# FlashPanelV6_2.net
KiCad netlist of a schematic drawn in EAGLE
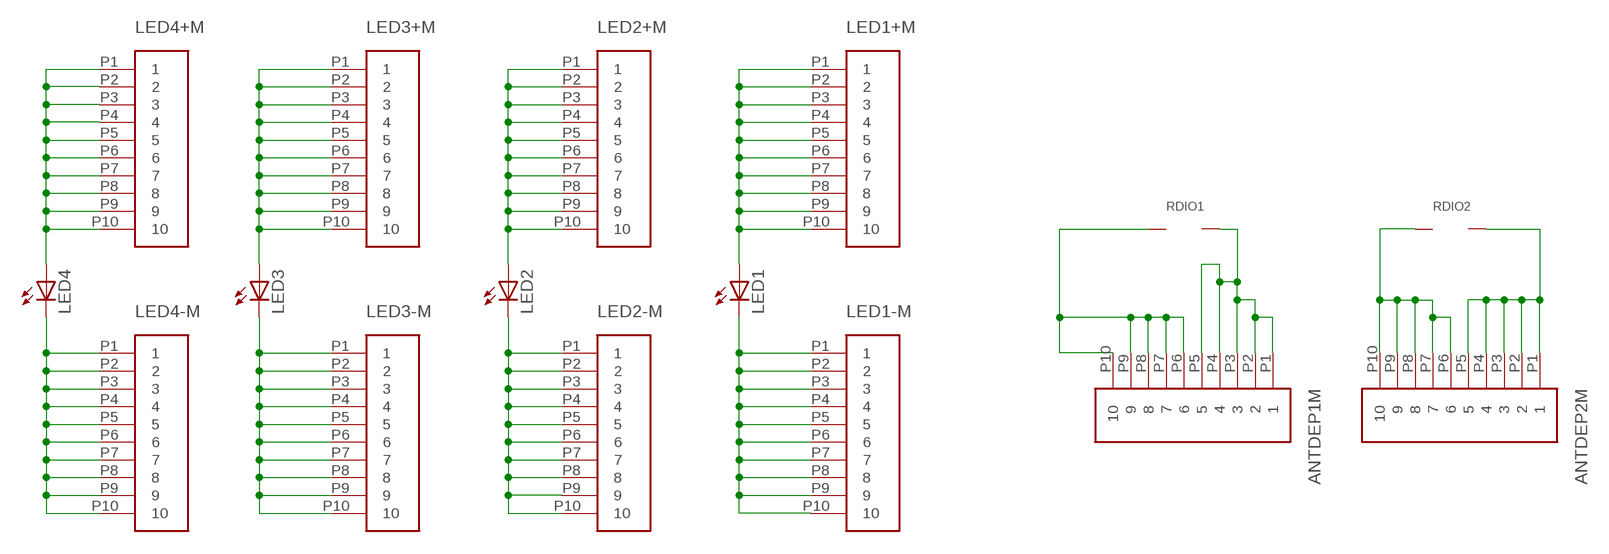
[diagram p0: schematic, sheet 1, part 1 of 2]
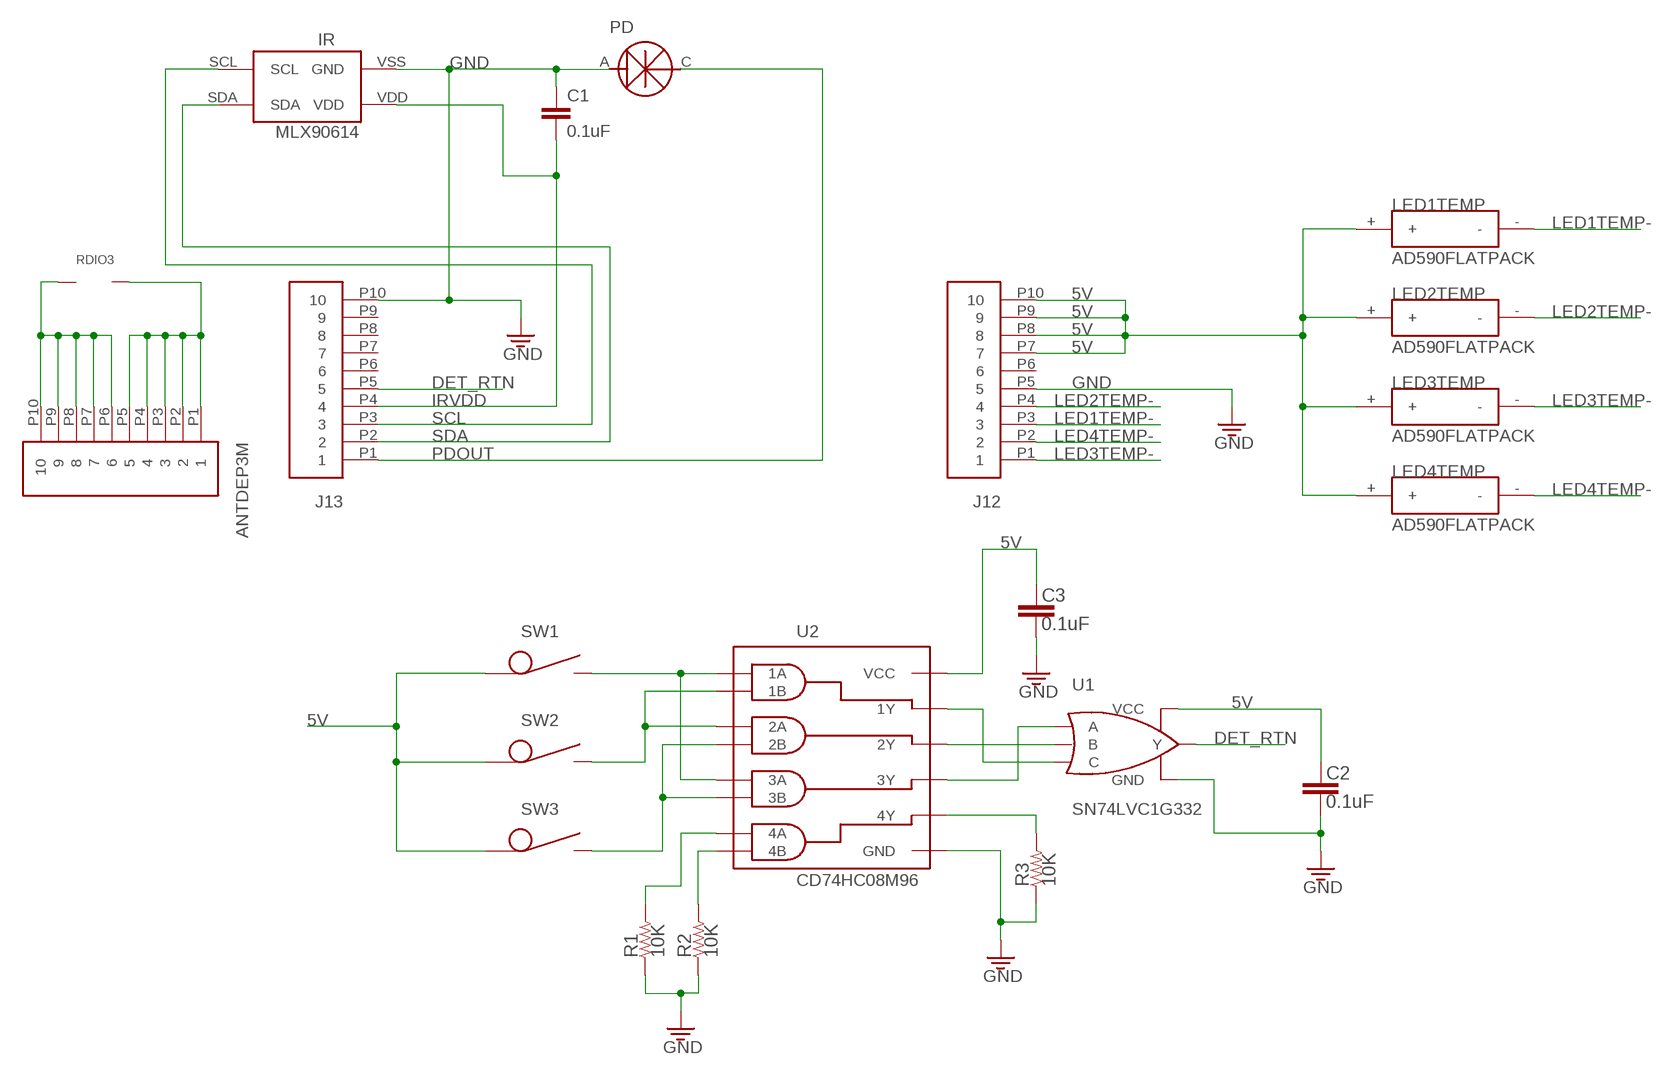
[diagram p1: schematic, sheet 1, part 2 of 2]

(export (version "E")
  (design (tool "Eeschema 10.0.6"))
  (components
    (comp (ref "ANTDEP1M")
      (value "10PINMALE")
      (footprint "eagle-import:10PINMALE")
      (libsource (lib "eagle-import") (part "10PINMALE"))
    )
    (comp (ref "ANTDEP2M")
      (value "10PINMALE")
      (footprint "eagle-import:10PINMALE")
      (libsource (lib "eagle-import") (part "10PINMALE"))
    )
    (comp (ref "ANTDEP3M")
      (value "10PINMALE")
      (footprint "eagle-import:10PINMALE")
      (libsource (lib "eagle-import") (part "10PINMALE"))
    )
    (comp (ref "C1")
      (value "0.1uF")
      (footprint "eagle-import:0805")
      (libsource (lib "eagle-import") (part "CNTRL_BOARD_CAP0805"))
    )
    (comp (ref "C2")
      (value "0.1uF")
      (footprint "eagle-import:0805")
      (libsource (lib "eagle-import") (part "CAP0805"))
    )
    (comp (ref "C3")
      (value "0.1uF")
      (footprint "eagle-import:0805")
      (libsource (lib "eagle-import") (part "CAP0805"))
    )
    (comp (ref "IR")
      (value "MXL90614")
      (footprint "eagle-import:MXL90620")
      (libsource (lib "eagle-import") (part "MXL90614"))
    )
    (comp (ref "J12")
      (value "10PINMALE")
      (footprint "eagle-import:10PINMALE")
      (libsource (lib "eagle-import") (part "10PINMALE"))
    )
    (comp (ref "J13")
      (value "10PINMALE")
      (footprint "eagle-import:10PINMALE")
      (libsource (lib "eagle-import") (part "10PINMALE"))
    )
    (comp (ref "LED1")
      (value "CXM27")
      (footprint "eagle-import:CXM27")
      (libsource (lib "eagle-import") (part "CXM27"))
    )
    (comp (ref "LED1+M")
      (value "10PINMALE")
      (footprint "eagle-import:10PINMALE")
      (libsource (lib "eagle-import") (part "10PINMALE"))
    )
    (comp (ref "LED1-M")
      (value "10PINMALE")
      (footprint "eagle-import:10PINMALE")
      (libsource (lib "eagle-import") (part "10PINMALE"))
    )
    (comp (ref "LED1TEMP")
      (value "AD590FLATPACK")
      (footprint "eagle-import:FLATPACK")
      (libsource (lib "eagle-import") (part "AD590FLATPACK"))
    )
    (comp (ref "LED2")
      (value "CXM27")
      (footprint "eagle-import:CXM27")
      (libsource (lib "eagle-import") (part "CXM27"))
    )
    (comp (ref "LED2+M")
      (value "10PINMALE")
      (footprint "eagle-import:10PINMALE")
      (libsource (lib "eagle-import") (part "10PINMALE"))
    )
    (comp (ref "LED2-M")
      (value "10PINMALE")
      (footprint "eagle-import:10PINMALE")
      (libsource (lib "eagle-import") (part "10PINMALE"))
    )
    (comp (ref "LED2TEMP")
      (value "AD590FLATPACK")
      (footprint "eagle-import:FLATPACK")
      (libsource (lib "eagle-import") (part "AD590FLATPACK"))
    )
    (comp (ref "LED3")
      (value "CXM27")
      (footprint "eagle-import:CXM27")
      (libsource (lib "eagle-import") (part "CXM27"))
    )
    (comp (ref "LED3+M")
      (value "10PINMALE")
      (footprint "eagle-import:10PINMALE")
      (libsource (lib "eagle-import") (part "10PINMALE"))
    )
    (comp (ref "LED3-M")
      (value "10PINMALE")
      (footprint "eagle-import:10PINMALE")
      (libsource (lib "eagle-import") (part "10PINMALE"))
    )
    (comp (ref "LED3TEMP")
      (value "AD590FLATPACK")
      (footprint "eagle-import:FLATPACK")
      (libsource (lib "eagle-import") (part "AD590FLATPACK"))
    )
    (comp (ref "LED4")
      (value "CXM27")
      (footprint "eagle-import:CXM27")
      (libsource (lib "eagle-import") (part "CXM27"))
    )
    (comp (ref "LED4+M")
      (value "10PINMALE")
      (footprint "eagle-import:10PINMALE")
      (libsource (lib "eagle-import") (part "10PINMALE"))
    )
    (comp (ref "LED4-M")
      (value "10PINMALE")
      (footprint "eagle-import:10PINMALE")
      (libsource (lib "eagle-import") (part "10PINMALE"))
    )
    (comp (ref "LED4TEMP")
      (value "AD590FLATPACK")
      (footprint "eagle-import:FLATPACK")
      (libsource (lib "eagle-import") (part "AD590FLATPACK"))
    )
    (comp (ref "PD")
      (value "TEMD6200")
      (footprint "eagle-import:TEMD6200")
      (libsource (lib "eagle-import") (part "TEMD6200"))
    )
    (comp (ref "R1")
      (value "10K")
      (footprint "eagle-import:0805")
      (libsource (lib "eagle-import") (part "RES0805"))
    )
    (comp (ref "R2")
      (value "10K")
      (footprint "eagle-import:0805")
      (libsource (lib "eagle-import") (part "RES0805"))
    )
    (comp (ref "R3")
      (value "10K")
      (footprint "eagle-import:0805")
      (libsource (lib "eagle-import") (part "RES0805"))
    )
    (comp (ref "RDIO1")
      (value "RDIO")
      (footprint "eagle-import:RDIO_DPLY")
      (libsource (lib "eagle-import") (part "RDIO"))
    )
    (comp (ref "RDIO2")
      (value "RDIO")
      (footprint "eagle-import:RDIO_DPLY")
      (libsource (lib "eagle-import") (part "RDIO"))
    )
    (comp (ref "RDIO3")
      (value "RDIO")
      (footprint "eagle-import:RDIO_DPLY")
      (libsource (lib "eagle-import") (part "RDIO"))
    )
    (comp (ref "SW1")
      (value "SW-DETECT")
      (footprint "eagle-import:SW-SPRING")
      (libsource (lib "eagle-import") (part "SW-DETECT"))
    )
    (comp (ref "SW2")
      (value "SW-DETECT")
      (footprint "eagle-import:SW-SPRING")
      (libsource (lib "eagle-import") (part "SW-DETECT"))
    )
    (comp (ref "SW3")
      (value "SW-DETECT")
      (footprint "eagle-import:SW-SPRING")
      (libsource (lib "eagle-import") (part "SW-DETECT"))
    )
    (comp (ref "U1")
      (value "SN74LVC1G332")
      (footprint "eagle-import:DCK-6")
      (libsource (lib "eagle-import") (part "SN74LVC1G332"))
    )
    (comp (ref "U2")
      (value "CD74HC08M96")
      (footprint "eagle-import:SOIC-14")
      (libsource (lib "eagle-import") (part "CD74HC08M96"))
    )
  )
  (nets
    (net (code "1") (name "/5V") (class "Default")
      (node (ref "C2") (pin "1") (pinfunction "P$1_1") (pintype "passive"))
      (node (ref "C3") (pin "1") (pinfunction "P$1_1") (pintype "passive"))
      (node (ref "J12") (pin "P10") (pinfunction "10_P10") (pintype "bidirectional"))
      (node (ref "J12") (pin "P7") (pinfunction "7_P7") (pintype "bidirectional"))
      (node (ref "J12") (pin "P8") (pinfunction "8_P8") (pintype "bidirectional"))
      (node (ref "J12") (pin "P9") (pinfunction "9_P9") (pintype "bidirectional"))
      (node (ref "LED1TEMP") (pin "+") (pinfunction "+_+") (pintype "bidirectional"))
      (node (ref "LED2TEMP") (pin "+") (pinfunction "+_+") (pintype "bidirectional"))
      (node (ref "LED3TEMP") (pin "+") (pinfunction "+_+") (pintype "bidirectional"))
      (node (ref "LED4TEMP") (pin "+") (pinfunction "+_+") (pintype "bidirectional"))
      (node (ref "SW1") (pin "P$1") (pinfunction "P$1_P$1") (pintype "bidirectional"))
      (node (ref "SW2") (pin "P$1") (pinfunction "P$1_P$1") (pintype "bidirectional"))
      (node (ref "SW3") (pin "P$1") (pinfunction "P$1_P$1") (pintype "bidirectional"))
      (node (ref "U1") (pin "P$5") (pinfunction "VCC_P$5") (pintype "power_in"))
      (node (ref "U2") (pin "P$14") (pinfunction "VCC_P$14") (pintype "power_in"))
    )
    (net (code "2") (name "/DET_RTN") (class "Default")
      (node (ref "J13") (pin "P5") (pinfunction "5_P5") (pintype "bidirectional"))
      (node (ref "U1") (pin "P$4") (pinfunction "Y_P$4") (pintype "output"))
    )
    (net (code "3") (name "/IRVDD") (class "Default")
      (node (ref "C1") (pin "2") (pinfunction "2_2") (pintype "passive"))
      (node (ref "IR") (pin "VDD") (pinfunction "VDD_VDD") (pintype "bidirectional"))
      (node (ref "J13") (pin "P4") (pinfunction "4_P4") (pintype "bidirectional"))
    )
    (net (code "4") (name "/LED1TEMP-") (class "Default")
      (node (ref "J12") (pin "P3") (pinfunction "3_P3") (pintype "bidirectional"))
      (node (ref "LED1TEMP") (pin "-") (pinfunction "-_-") (pintype "bidirectional"))
    )
    (net (code "5") (name "/LED2TEMP-") (class "Default")
      (node (ref "J12") (pin "P4") (pinfunction "4_P4") (pintype "bidirectional"))
      (node (ref "LED2TEMP") (pin "-") (pinfunction "-_-") (pintype "bidirectional"))
    )
    (net (code "6") (name "/LED3TEMP-") (class "Default")
      (node (ref "J12") (pin "P1") (pinfunction "1_P1") (pintype "bidirectional"))
      (node (ref "LED3TEMP") (pin "-") (pinfunction "-_-") (pintype "bidirectional"))
    )
    (net (code "7") (name "/LED4TEMP-") (class "Default")
      (node (ref "J12") (pin "P2") (pinfunction "2_P2") (pintype "bidirectional"))
      (node (ref "LED4TEMP") (pin "-") (pinfunction "-_-") (pintype "bidirectional"))
    )
    (net (code "8") (name "/PDOUT") (class "Default")
      (node (ref "J13") (pin "P1") (pinfunction "1_P1") (pintype "bidirectional"))
      (node (ref "PD") (pin "C") (pinfunction "C_C") (pintype "bidirectional"))
    )
    (net (code "9") (name "/SCL") (class "Default")
      (node (ref "IR") (pin "SCL") (pinfunction "SCL_SCL") (pintype "bidirectional"))
      (node (ref "J13") (pin "P3") (pinfunction "3_P3") (pintype "bidirectional"))
    )
    (net (code "10") (name "/SDA") (class "Default")
      (node (ref "IR") (pin "SDA") (pinfunction "SDA_SDA") (pintype "bidirectional"))
      (node (ref "J13") (pin "P2") (pinfunction "2_P2") (pintype "bidirectional"))
    )
    (net (code "11") (name "GND") (class "Default")
      (node (ref "C1") (pin "1") (pinfunction "1_1") (pintype "passive"))
      (node (ref "C2") (pin "2") (pinfunction "P$2_2") (pintype "passive"))
      (node (ref "C3") (pin "2") (pinfunction "P$2_2") (pintype "passive"))
      (node (ref "IR") (pin "VSS") (pinfunction "GND_VSS") (pintype "bidirectional"))
      (node (ref "J12") (pin "P5") (pinfunction "5_P5") (pintype "bidirectional"))
      (node (ref "J13") (pin "P10") (pinfunction "10_P10") (pintype "bidirectional"))
      (node (ref "PD") (pin "A") (pinfunction "A_A") (pintype "bidirectional"))
      (node (ref "R1") (pin "1") (pinfunction "1_1") (pintype "passive"))
      (node (ref "R2") (pin "1") (pinfunction "1_1") (pintype "passive"))
      (node (ref "R3") (pin "1") (pinfunction "1_1") (pintype "passive"))
      (node (ref "U1") (pin "P$2") (pinfunction "GND_P$2") (pintype "power_in"))
      (node (ref "U2") (pin "P$7") (pinfunction "GND_P$7") (pintype "power_in"))
    )
    (net (code "12") (name "Net-(ANTDEP1M-1)") (class "Default")
      (node (ref "ANTDEP1M") (pin "P1") (pinfunction "1_P1") (pintype "bidirectional"))
      (node (ref "ANTDEP1M") (pin "P2") (pinfunction "2_P2") (pintype "bidirectional"))
      (node (ref "ANTDEP1M") (pin "P3") (pinfunction "3_P3") (pintype "bidirectional"))
      (node (ref "ANTDEP1M") (pin "P4") (pinfunction "4_P4") (pintype "bidirectional"))
      (node (ref "ANTDEP1M") (pin "P5") (pinfunction "5_P5") (pintype "bidirectional"))
      (node (ref "RDIO1") (pin "P1") (pinfunction "P$1_P1") (pintype "bidirectional"))
      (node (ref "RDIO1") (pin "P2") (pinfunction "P$1_P2") (pintype "bidirectional"))
    )
    (net (code "13") (name "Net-(ANTDEP1M-10)") (class "Default")
      (node (ref "ANTDEP1M") (pin "P10") (pinfunction "10_P10") (pintype "bidirectional"))
      (node (ref "ANTDEP1M") (pin "P6") (pinfunction "6_P6") (pintype "bidirectional"))
      (node (ref "ANTDEP1M") (pin "P7") (pinfunction "7_P7") (pintype "bidirectional"))
      (node (ref "ANTDEP1M") (pin "P8") (pinfunction "8_P8") (pintype "bidirectional"))
      (node (ref "ANTDEP1M") (pin "P9") (pinfunction "9_P9") (pintype "bidirectional"))
      (node (ref "RDIO1") (pin "P3") (pinfunction "P$2_P3") (pintype "bidirectional"))
      (node (ref "RDIO1") (pin "P4") (pinfunction "P$2_P4") (pintype "bidirectional"))
    )
    (net (code "14") (name "Net-(ANTDEP2M-1)") (class "Default")
      (node (ref "ANTDEP2M") (pin "P1") (pinfunction "1_P1") (pintype "bidirectional"))
      (node (ref "ANTDEP2M") (pin "P2") (pinfunction "2_P2") (pintype "bidirectional"))
      (node (ref "ANTDEP2M") (pin "P3") (pinfunction "3_P3") (pintype "bidirectional"))
      (node (ref "ANTDEP2M") (pin "P4") (pinfunction "4_P4") (pintype "bidirectional"))
      (node (ref "ANTDEP2M") (pin "P5") (pinfunction "5_P5") (pintype "bidirectional"))
      (node (ref "RDIO2") (pin "P1") (pinfunction "P$1_P1") (pintype "bidirectional"))
      (node (ref "RDIO2") (pin "P2") (pinfunction "P$1_P2") (pintype "bidirectional"))
    )
    (net (code "15") (name "Net-(ANTDEP2M-10)") (class "Default")
      (node (ref "ANTDEP2M") (pin "P10") (pinfunction "10_P10") (pintype "bidirectional"))
      (node (ref "ANTDEP2M") (pin "P6") (pinfunction "6_P6") (pintype "bidirectional"))
      (node (ref "ANTDEP2M") (pin "P7") (pinfunction "7_P7") (pintype "bidirectional"))
      (node (ref "ANTDEP2M") (pin "P8") (pinfunction "8_P8") (pintype "bidirectional"))
      (node (ref "ANTDEP2M") (pin "P9") (pinfunction "9_P9") (pintype "bidirectional"))
      (node (ref "RDIO2") (pin "P3") (pinfunction "P$2_P3") (pintype "bidirectional"))
      (node (ref "RDIO2") (pin "P4") (pinfunction "P$2_P4") (pintype "bidirectional"))
    )
    (net (code "16") (name "Net-(ANTDEP3M-1)") (class "Default")
      (node (ref "ANTDEP3M") (pin "P1") (pinfunction "1_P1") (pintype "bidirectional"))
      (node (ref "ANTDEP3M") (pin "P2") (pinfunction "2_P2") (pintype "bidirectional"))
      (node (ref "ANTDEP3M") (pin "P3") (pinfunction "3_P3") (pintype "bidirectional"))
      (node (ref "ANTDEP3M") (pin "P4") (pinfunction "4_P4") (pintype "bidirectional"))
      (node (ref "ANTDEP3M") (pin "P5") (pinfunction "5_P5") (pintype "bidirectional"))
      (node (ref "RDIO3") (pin "P1") (pinfunction "P$1_P1") (pintype "bidirectional"))
      (node (ref "RDIO3") (pin "P2") (pinfunction "P$1_P2") (pintype "bidirectional"))
    )
    (net (code "17") (name "Net-(ANTDEP3M-10)") (class "Default")
      (node (ref "ANTDEP3M") (pin "P10") (pinfunction "10_P10") (pintype "bidirectional"))
      (node (ref "ANTDEP3M") (pin "P6") (pinfunction "6_P6") (pintype "bidirectional"))
      (node (ref "ANTDEP3M") (pin "P7") (pinfunction "7_P7") (pintype "bidirectional"))
      (node (ref "ANTDEP3M") (pin "P8") (pinfunction "8_P8") (pintype "bidirectional"))
      (node (ref "ANTDEP3M") (pin "P9") (pinfunction "9_P9") (pintype "bidirectional"))
      (node (ref "RDIO3") (pin "P3") (pinfunction "P$2_P3") (pintype "bidirectional"))
      (node (ref "RDIO3") (pin "P4") (pinfunction "P$2_P4") (pintype "bidirectional"))
    )
    (net (code "18") (name "Net-(LED1+M-1)") (class "Default")
      (node (ref "LED1") (pin "ANODE") (pinfunction "A_ANODE") (pintype "passive"))
      (node (ref "LED1+M") (pin "P1") (pinfunction "1_P1") (pintype "bidirectional"))
      (node (ref "LED1+M") (pin "P10") (pinfunction "10_P10") (pintype "bidirectional"))
      (node (ref "LED1+M") (pin "P2") (pinfunction "2_P2") (pintype "bidirectional"))
      (node (ref "LED1+M") (pin "P3") (pinfunction "3_P3") (pintype "bidirectional"))
      (node (ref "LED1+M") (pin "P4") (pinfunction "4_P4") (pintype "bidirectional"))
      (node (ref "LED1+M") (pin "P5") (pinfunction "5_P5") (pintype "bidirectional"))
      (node (ref "LED1+M") (pin "P6") (pinfunction "6_P6") (pintype "bidirectional"))
      (node (ref "LED1+M") (pin "P7") (pinfunction "7_P7") (pintype "bidirectional"))
      (node (ref "LED1+M") (pin "P8") (pinfunction "8_P8") (pintype "bidirectional"))
      (node (ref "LED1+M") (pin "P9") (pinfunction "9_P9") (pintype "bidirectional"))
    )
    (net (code "19") (name "Net-(LED1-C)") (class "Default")
      (node (ref "LED1") (pin "CATHODE") (pinfunction "C_CATHODE") (pintype "passive"))
      (node (ref "LED1-M") (pin "P1") (pinfunction "1_P1") (pintype "bidirectional"))
      (node (ref "LED1-M") (pin "P10") (pinfunction "10_P10") (pintype "bidirectional"))
      (node (ref "LED1-M") (pin "P2") (pinfunction "2_P2") (pintype "bidirectional"))
      (node (ref "LED1-M") (pin "P3") (pinfunction "3_P3") (pintype "bidirectional"))
      (node (ref "LED1-M") (pin "P4") (pinfunction "4_P4") (pintype "bidirectional"))
      (node (ref "LED1-M") (pin "P5") (pinfunction "5_P5") (pintype "bidirectional"))
      (node (ref "LED1-M") (pin "P6") (pinfunction "6_P6") (pintype "bidirectional"))
      (node (ref "LED1-M") (pin "P7") (pinfunction "7_P7") (pintype "bidirectional"))
      (node (ref "LED1-M") (pin "P8") (pinfunction "8_P8") (pintype "bidirectional"))
      (node (ref "LED1-M") (pin "P9") (pinfunction "9_P9") (pintype "bidirectional"))
    )
    (net (code "20") (name "Net-(LED2+M-1)") (class "Default")
      (node (ref "LED2") (pin "ANODE") (pinfunction "A_ANODE") (pintype "passive"))
      (node (ref "LED2+M") (pin "P1") (pinfunction "1_P1") (pintype "bidirectional"))
      (node (ref "LED2+M") (pin "P10") (pinfunction "10_P10") (pintype "bidirectional"))
      (node (ref "LED2+M") (pin "P2") (pinfunction "2_P2") (pintype "bidirectional"))
      (node (ref "LED2+M") (pin "P3") (pinfunction "3_P3") (pintype "bidirectional"))
      (node (ref "LED2+M") (pin "P4") (pinfunction "4_P4") (pintype "bidirectional"))
      (node (ref "LED2+M") (pin "P5") (pinfunction "5_P5") (pintype "bidirectional"))
      (node (ref "LED2+M") (pin "P6") (pinfunction "6_P6") (pintype "bidirectional"))
      (node (ref "LED2+M") (pin "P7") (pinfunction "7_P7") (pintype "bidirectional"))
      (node (ref "LED2+M") (pin "P8") (pinfunction "8_P8") (pintype "bidirectional"))
      (node (ref "LED2+M") (pin "P9") (pinfunction "9_P9") (pintype "bidirectional"))
    )
    (net (code "21") (name "Net-(LED2-C)") (class "Default")
      (node (ref "LED2") (pin "CATHODE") (pinfunction "C_CATHODE") (pintype "passive"))
      (node (ref "LED2-M") (pin "P1") (pinfunction "1_P1") (pintype "bidirectional"))
      (node (ref "LED2-M") (pin "P10") (pinfunction "10_P10") (pintype "bidirectional"))
      (node (ref "LED2-M") (pin "P2") (pinfunction "2_P2") (pintype "bidirectional"))
      (node (ref "LED2-M") (pin "P3") (pinfunction "3_P3") (pintype "bidirectional"))
      (node (ref "LED2-M") (pin "P4") (pinfunction "4_P4") (pintype "bidirectional"))
      (node (ref "LED2-M") (pin "P5") (pinfunction "5_P5") (pintype "bidirectional"))
      (node (ref "LED2-M") (pin "P6") (pinfunction "6_P6") (pintype "bidirectional"))
      (node (ref "LED2-M") (pin "P7") (pinfunction "7_P7") (pintype "bidirectional"))
      (node (ref "LED2-M") (pin "P8") (pinfunction "8_P8") (pintype "bidirectional"))
      (node (ref "LED2-M") (pin "P9") (pinfunction "9_P9") (pintype "bidirectional"))
    )
    (net (code "22") (name "Net-(LED3+M-1)") (class "Default")
      (node (ref "LED3") (pin "ANODE") (pinfunction "A_ANODE") (pintype "passive"))
      (node (ref "LED3+M") (pin "P1") (pinfunction "1_P1") (pintype "bidirectional"))
      (node (ref "LED3+M") (pin "P10") (pinfunction "10_P10") (pintype "bidirectional"))
      (node (ref "LED3+M") (pin "P2") (pinfunction "2_P2") (pintype "bidirectional"))
      (node (ref "LED3+M") (pin "P3") (pinfunction "3_P3") (pintype "bidirectional"))
      (node (ref "LED3+M") (pin "P4") (pinfunction "4_P4") (pintype "bidirectional"))
      (node (ref "LED3+M") (pin "P5") (pinfunction "5_P5") (pintype "bidirectional"))
      (node (ref "LED3+M") (pin "P6") (pinfunction "6_P6") (pintype "bidirectional"))
      (node (ref "LED3+M") (pin "P7") (pinfunction "7_P7") (pintype "bidirectional"))
      (node (ref "LED3+M") (pin "P8") (pinfunction "8_P8") (pintype "bidirectional"))
      (node (ref "LED3+M") (pin "P9") (pinfunction "9_P9") (pintype "bidirectional"))
    )
    (net (code "23") (name "Net-(LED3-C)") (class "Default")
      (node (ref "LED3") (pin "CATHODE") (pinfunction "C_CATHODE") (pintype "passive"))
      (node (ref "LED3-M") (pin "P1") (pinfunction "1_P1") (pintype "bidirectional"))
      (node (ref "LED3-M") (pin "P10") (pinfunction "10_P10") (pintype "bidirectional"))
      (node (ref "LED3-M") (pin "P2") (pinfunction "2_P2") (pintype "bidirectional"))
      (node (ref "LED3-M") (pin "P3") (pinfunction "3_P3") (pintype "bidirectional"))
      (node (ref "LED3-M") (pin "P4") (pinfunction "4_P4") (pintype "bidirectional"))
      (node (ref "LED3-M") (pin "P5") (pinfunction "5_P5") (pintype "bidirectional"))
      (node (ref "LED3-M") (pin "P6") (pinfunction "6_P6") (pintype "bidirectional"))
      (node (ref "LED3-M") (pin "P7") (pinfunction "7_P7") (pintype "bidirectional"))
      (node (ref "LED3-M") (pin "P8") (pinfunction "8_P8") (pintype "bidirectional"))
      (node (ref "LED3-M") (pin "P9") (pinfunction "9_P9") (pintype "bidirectional"))
    )
    (net (code "24") (name "Net-(LED4+M-1)") (class "Default")
      (node (ref "LED4") (pin "ANODE") (pinfunction "A_ANODE") (pintype "passive"))
      (node (ref "LED4+M") (pin "P1") (pinfunction "1_P1") (pintype "bidirectional"))
      (node (ref "LED4+M") (pin "P10") (pinfunction "10_P10") (pintype "bidirectional"))
      (node (ref "LED4+M") (pin "P2") (pinfunction "2_P2") (pintype "bidirectional"))
      (node (ref "LED4+M") (pin "P3") (pinfunction "3_P3") (pintype "bidirectional"))
      (node (ref "LED4+M") (pin "P4") (pinfunction "4_P4") (pintype "bidirectional"))
      (node (ref "LED4+M") (pin "P5") (pinfunction "5_P5") (pintype "bidirectional"))
      (node (ref "LED4+M") (pin "P6") (pinfunction "6_P6") (pintype "bidirectional"))
      (node (ref "LED4+M") (pin "P7") (pinfunction "7_P7") (pintype "bidirectional"))
      (node (ref "LED4+M") (pin "P8") (pinfunction "8_P8") (pintype "bidirectional"))
      (node (ref "LED4+M") (pin "P9") (pinfunction "9_P9") (pintype "bidirectional"))
    )
    (net (code "25") (name "Net-(LED4-C)") (class "Default")
      (node (ref "LED4") (pin "CATHODE") (pinfunction "C_CATHODE") (pintype "passive"))
      (node (ref "LED4-M") (pin "P1") (pinfunction "1_P1") (pintype "bidirectional"))
      (node (ref "LED4-M") (pin "P10") (pinfunction "10_P10") (pintype "bidirectional"))
      (node (ref "LED4-M") (pin "P2") (pinfunction "2_P2") (pintype "bidirectional"))
      (node (ref "LED4-M") (pin "P3") (pinfunction "3_P3") (pintype "bidirectional"))
      (node (ref "LED4-M") (pin "P4") (pinfunction "4_P4") (pintype "bidirectional"))
      (node (ref "LED4-M") (pin "P5") (pinfunction "5_P5") (pintype "bidirectional"))
      (node (ref "LED4-M") (pin "P6") (pinfunction "6_P6") (pintype "bidirectional"))
      (node (ref "LED4-M") (pin "P7") (pinfunction "7_P7") (pintype "bidirectional"))
      (node (ref "LED4-M") (pin "P8") (pinfunction "8_P8") (pintype "bidirectional"))
      (node (ref "LED4-M") (pin "P9") (pinfunction "9_P9") (pintype "bidirectional"))
    )
    (net (code "26") (name "Net-(U1-A)") (class "Default")
      (node (ref "U1") (pin "P$1") (pinfunction "A_P$1") (pintype "input"))
      (node (ref "U2") (pin "P$8") (pinfunction "3Y_P$8") (pintype "output"))
    )
    (net (code "27") (name "Net-(U1-B)") (class "Default")
      (node (ref "U1") (pin "P$3") (pinfunction "B_P$3") (pintype "input"))
      (node (ref "U2") (pin "P$6") (pinfunction "2Y_P$6") (pintype "output"))
    )
    (net (code "28") (name "Net-(U1-C)") (class "Default")
      (node (ref "U1") (pin "P$6") (pinfunction "C_P$6") (pintype "input"))
      (node (ref "U2") (pin "P$3") (pinfunction "1Y_P$3") (pintype "output"))
    )
    (net (code "29") (name "Net-(U2-1A)") (class "Default")
      (node (ref "SW1") (pin "P$2") (pinfunction "P$2_P$2") (pintype "bidirectional"))
      (node (ref "U2") (pin "P$1") (pinfunction "1A_P$1") (pintype "input"))
      (node (ref "U2") (pin "P$9") (pinfunction "3A_P$9") (pintype "input"))
    )
    (net (code "30") (name "Net-(U2-1B)") (class "Default")
      (node (ref "SW2") (pin "P$2") (pinfunction "P$2_P$2") (pintype "bidirectional"))
      (node (ref "U2") (pin "P$2") (pinfunction "1B_P$2") (pintype "input"))
      (node (ref "U2") (pin "P$4") (pinfunction "2A_P$4") (pintype "input"))
    )
    (net (code "31") (name "Net-(U2-2B)") (class "Default")
      (node (ref "SW3") (pin "P$2") (pinfunction "P$2_P$2") (pintype "bidirectional"))
      (node (ref "U2") (pin "P$10") (pinfunction "3B_P$10") (pintype "input"))
      (node (ref "U2") (pin "P$5") (pinfunction "2B_P$5") (pintype "input"))
    )
    (net (code "32") (name "Net-(U2-4A)") (class "Default")
      (node (ref "R1") (pin "2") (pinfunction "2_2") (pintype "passive"))
      (node (ref "U2") (pin "P$12") (pinfunction "4A_P$12") (pintype "input"))
    )
    (net (code "33") (name "Net-(U2-4B)") (class "Default")
      (node (ref "R2") (pin "2") (pinfunction "2_2") (pintype "passive"))
      (node (ref "U2") (pin "P$13") (pinfunction "4B_P$13") (pintype "input"))
    )
    (net (code "34") (name "Net-(U2-4Y)") (class "Default")
      (node (ref "R3") (pin "2") (pinfunction "2_2") (pintype "passive"))
      (node (ref "U2") (pin "P$11") (pinfunction "4Y_P$11") (pintype "output"))
    )
    (net (code "35") (name "unconnected-(J12-6-PadP6)") (class "Default")
      (node (ref "J12") (pin "P6") (pinfunction "6_P6") (pintype "bidirectional"))
    )
    (net (code "36") (name "unconnected-(J13-6-PadP6)") (class "Default")
      (node (ref "J13") (pin "P6") (pinfunction "6_P6") (pintype "bidirectional"))
    )
    (net (code "37") (name "unconnected-(J13-7-PadP7)") (class "Default")
      (node (ref "J13") (pin "P7") (pinfunction "7_P7") (pintype "bidirectional"))
    )
    (net (code "38") (name "unconnected-(J13-8-PadP8)") (class "Default")
      (node (ref "J13") (pin "P8") (pinfunction "8_P8") (pintype "bidirectional"))
    )
    (net (code "39") (name "unconnected-(J13-9-PadP9)") (class "Default")
      (node (ref "J13") (pin "P9") (pinfunction "9_P9") (pintype "bidirectional"))
    )
  )
)
